# PiLoraGatewayV2_6.net
KiCad netlist of a schematic drawn in EAGLE
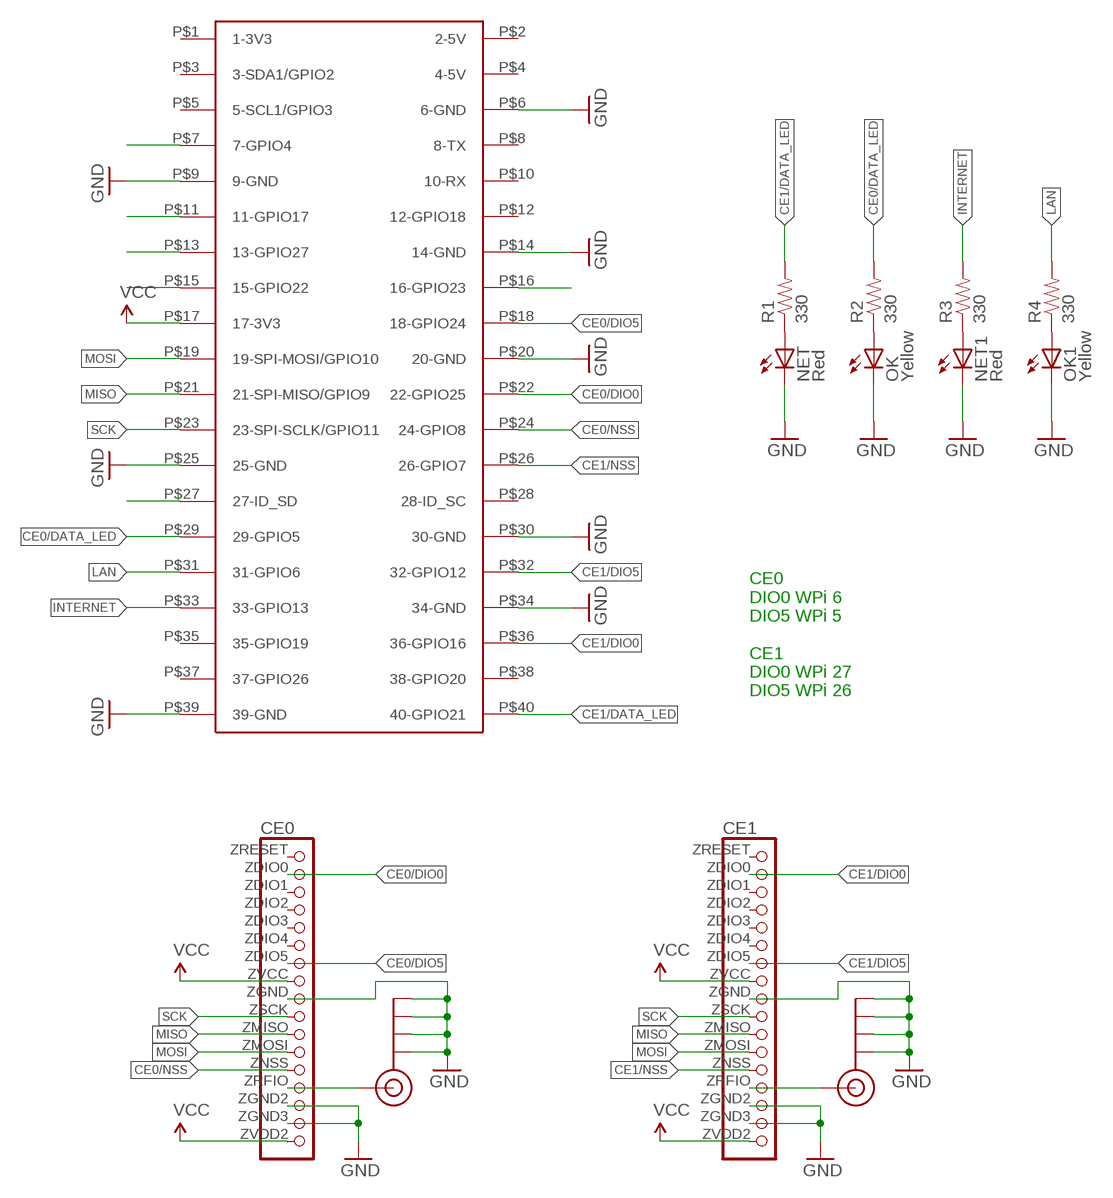
[diagram p0: schematic, sheet 1]

(export (version "E")
  (design (tool "Eeschema 10.0.6"))
  (components
    (comp (ref "CE0")
      (value "DRF1278F_BKOUTDP1276")
      (footprint "eagle-import:ANYLINK_DP1276")
      (libsource (lib "eagle-import") (part "DRF1278F_BKOUTDP1276"))
    )
    (comp (ref "CE1")
      (value "DRF1278F_BKOUTDP1276")
      (footprint "eagle-import:ANYLINK_DP1276")
      (libsource (lib "eagle-import") (part "DRF1278F_BKOUTDP1276"))
    )
    (comp (ref "J$1")
      (value "SMA_EDGE")
      (footprint "eagle-import:SMA-EDGE")
      (libsource (lib "eagle-import") (part "SMA_EDGE"))
    )
    (comp (ref "J$2")
      (value "SMA_EDGE")
      (footprint "eagle-import:SMA-EDGE")
      (libsource (lib "eagle-import") (part "SMA_EDGE"))
    )
    (comp (ref "NET")
      (value "Red")
      (footprint "eagle-import:LED-0603")
      (libsource (lib "eagle-import") (part "LED0603"))
    )
    (comp (ref "NET1")
      (value "Red")
      (footprint "eagle-import:LED-0603")
      (libsource (lib "eagle-import") (part "LED0603"))
    )
    (comp (ref "OK")
      (value "Yellow")
      (footprint "eagle-import:LED-0603")
      (libsource (lib "eagle-import") (part "LED0603"))
    )
    (comp (ref "OK1")
      (value "Yellow")
      (footprint "eagle-import:LED-0603")
      (libsource (lib "eagle-import") (part "LED0603"))
    )
    (comp (ref "R1")
      (value "330")
      (footprint "eagle-import:0603-RES")
      (libsource (lib "eagle-import") (part "RESISTOR0603-RES"))
    )
    (comp (ref "R2")
      (value "330")
      (footprint "eagle-import:0603-RES")
      (libsource (lib "eagle-import") (part "RESISTOR0603-RES"))
    )
    (comp (ref "R3")
      (value "330")
      (footprint "eagle-import:0603-RES")
      (libsource (lib "eagle-import") (part "RESISTOR0603-RES"))
    )
    (comp (ref "R4")
      (value "330")
      (footprint "eagle-import:0603-RES")
      (libsource (lib "eagle-import") (part "RESISTOR0603-RES"))
    )
    (comp (ref "U$1")
      (value "RASPBERRY-PI+")
      (footprint "eagle-import:RASPBERRY-PI-PLUS-CAM_NOTCH")
      (libsource (lib "eagle-import") (part "RASPBERRY-PI+"))
    )
  )
  (nets
    (net (code "1") (name "CE0{slash}DATA_LED") (class "Default")
      (node (ref "R2") (pin "2") (pinfunction "2_2") (pintype "passive"))
      (node (ref "U$1") (pin "P$29") (pinfunction "29-GPIO5_P$29") (pintype "bidirectional"))
    )
    (net (code "2") (name "CE0{slash}DIO0") (class "Default")
      (node (ref "CE0") (pin "ZDIO0") (pinfunction "DIO0_ZDIO0") (pintype "passive"))
      (node (ref "U$1") (pin "P$22") (pinfunction "22-GPIO25_P$22") (pintype "bidirectional"))
    )
    (net (code "3") (name "CE0{slash}DIO5") (class "Default")
      (node (ref "CE0") (pin "ZDIO5") (pinfunction "DIO5_ZDIO5") (pintype "passive"))
      (node (ref "U$1") (pin "P$18") (pinfunction "18-GPIO24_P$18") (pintype "bidirectional"))
    )
    (net (code "4") (name "CE0{slash}NSS") (class "Default")
      (node (ref "CE0") (pin "ZNSS") (pinfunction "NSS_ZNSS") (pintype "passive"))
      (node (ref "U$1") (pin "P$24") (pinfunction "24-GPIO8_P$24") (pintype "bidirectional"))
    )
    (net (code "5") (name "CE1{slash}DATA_LED") (class "Default")
      (node (ref "R1") (pin "2") (pinfunction "2_2") (pintype "passive"))
      (node (ref "U$1") (pin "P$40") (pinfunction "40-GPIO21_P$40") (pintype "bidirectional"))
    )
    (net (code "6") (name "CE1{slash}DIO0") (class "Default")
      (node (ref "CE1") (pin "ZDIO0") (pinfunction "DIO0_ZDIO0") (pintype "passive"))
      (node (ref "U$1") (pin "P$36") (pinfunction "36-GPIO16_P$36") (pintype "bidirectional"))
    )
    (net (code "7") (name "CE1{slash}DIO5") (class "Default")
      (node (ref "CE1") (pin "ZDIO5") (pinfunction "DIO5_ZDIO5") (pintype "passive"))
      (node (ref "U$1") (pin "P$32") (pinfunction "32-GPIO12_P$32") (pintype "bidirectional"))
    )
    (net (code "8") (name "CE1{slash}NSS") (class "Default")
      (node (ref "CE1") (pin "ZNSS") (pinfunction "NSS_ZNSS") (pintype "passive"))
      (node (ref "U$1") (pin "P$26") (pinfunction "26-GPIO7_P$26") (pintype "bidirectional"))
    )
    (net (code "9") (name "GND") (class "Default")
      (node (ref "CE0") (pin "ZGND") (pinfunction "GND_ZGND") (pintype "passive"))
      (node (ref "CE0") (pin "ZGND2") (pinfunction "RGND1_ZGND2") (pintype "passive"))
      (node (ref "CE0") (pin "ZGND3") (pinfunction "RGND2_ZGND3") (pintype "passive"))
      (node (ref "CE1") (pin "ZGND") (pinfunction "GND_ZGND") (pintype "passive"))
      (node (ref "CE1") (pin "ZGND2") (pinfunction "RGND1_ZGND2") (pintype "passive"))
      (node (ref "CE1") (pin "ZGND3") (pinfunction "RGND2_ZGND3") (pintype "passive"))
      (node (ref "J$1") (pin "GND@0") (pinfunction "GND_GND@0") (pintype "bidirectional"))
      (node (ref "J$1") (pin "GND@1") (pinfunction "GND_GND@1") (pintype "bidirectional"))
      (node (ref "J$1") (pin "GND@2") (pinfunction "GND_GND@2") (pintype "bidirectional"))
      (node (ref "J$1") (pin "GND@3") (pinfunction "GND_GND@3") (pintype "bidirectional"))
      (node (ref "J$2") (pin "GND@0") (pinfunction "GND_GND@0") (pintype "bidirectional"))
      (node (ref "J$2") (pin "GND@1") (pinfunction "GND_GND@1") (pintype "bidirectional"))
      (node (ref "J$2") (pin "GND@2") (pinfunction "GND_GND@2") (pintype "bidirectional"))
      (node (ref "J$2") (pin "GND@3") (pinfunction "GND_GND@3") (pintype "bidirectional"))
      (node (ref "NET") (pin "C") (pinfunction "C_C") (pintype "passive"))
      (node (ref "NET1") (pin "C") (pinfunction "C_C") (pintype "passive"))
      (node (ref "OK") (pin "C") (pinfunction "C_C") (pintype "passive"))
      (node (ref "OK1") (pin "C") (pinfunction "C_C") (pintype "passive"))
      (node (ref "U$1") (pin "P$14") (pinfunction "14-GND_P$14") (pintype "bidirectional"))
      (node (ref "U$1") (pin "P$20") (pinfunction "20-GND_P$20") (pintype "bidirectional"))
      (node (ref "U$1") (pin "P$25") (pinfunction "25-GND_P$25") (pintype "bidirectional"))
      (node (ref "U$1") (pin "P$30") (pinfunction "30-GND_P$30") (pintype "bidirectional"))
      (node (ref "U$1") (pin "P$34") (pinfunction "34-GND_P$34") (pintype "bidirectional"))
      (node (ref "U$1") (pin "P$39") (pinfunction "39-GND_P$39") (pintype "bidirectional"))
      (node (ref "U$1") (pin "P$6") (pinfunction "6-GND_P$6") (pintype "bidirectional"))
      (node (ref "U$1") (pin "P$9") (pinfunction "9-GND_P$9") (pintype "bidirectional"))
    )
    (net (code "10") (name "INTERNET") (class "Default")
      (node (ref "R3") (pin "2") (pinfunction "2_2") (pintype "passive"))
      (node (ref "U$1") (pin "P$33") (pinfunction "33-GPIO13_P$33") (pintype "bidirectional"))
    )
    (net (code "11") (name "LAN") (class "Default")
      (node (ref "R4") (pin "2") (pinfunction "2_2") (pintype "passive"))
      (node (ref "U$1") (pin "P$31") (pinfunction "31-GPIO6_P$31") (pintype "bidirectional"))
    )
    (net (code "12") (name "MISO") (class "Default")
      (node (ref "CE0") (pin "ZMISO") (pinfunction "MISO_ZMISO") (pintype "passive"))
      (node (ref "CE1") (pin "ZMISO") (pinfunction "MISO_ZMISO") (pintype "passive"))
      (node (ref "U$1") (pin "P$21") (pinfunction "21-SPI-MISO/GPIO9_P$21") (pintype "bidirectional"))
    )
    (net (code "13") (name "MOSI") (class "Default")
      (node (ref "CE0") (pin "ZMOSI") (pinfunction "MOSI_ZMOSI") (pintype "passive"))
      (node (ref "CE1") (pin "ZMOSI") (pinfunction "MOSI_ZMOSI") (pintype "passive"))
      (node (ref "U$1") (pin "P$19") (pinfunction "19-SPI-MOSI/GPIO10_P$19") (pintype "bidirectional"))
    )
    (net (code "14") (name "Net-(CE0-RFIO)") (class "Default")
      (node (ref "CE0") (pin "ZRFIO") (pinfunction "RFIO_ZRFIO") (pintype "passive"))
      (node (ref "J$1") (pin "SIG") (pinfunction "SIGNAL_SIG") (pintype "bidirectional"))
    )
    (net (code "15") (name "Net-(CE1-RFIO)") (class "Default")
      (node (ref "CE1") (pin "ZRFIO") (pinfunction "RFIO_ZRFIO") (pintype "passive"))
      (node (ref "J$2") (pin "SIG") (pinfunction "SIGNAL_SIG") (pintype "bidirectional"))
    )
    (net (code "16") (name "Net-(NET-PadA)") (class "Default")
      (node (ref "NET") (pin "A") (pinfunction "A_A") (pintype "passive"))
      (node (ref "R1") (pin "1") (pinfunction "1_1") (pintype "passive"))
    )
    (net (code "17") (name "Net-(NET1-PadA)") (class "Default")
      (node (ref "NET1") (pin "A") (pinfunction "A_A") (pintype "passive"))
      (node (ref "R3") (pin "1") (pinfunction "1_1") (pintype "passive"))
    )
    (net (code "18") (name "Net-(OK-PadA)") (class "Default")
      (node (ref "OK") (pin "A") (pinfunction "A_A") (pintype "passive"))
      (node (ref "R2") (pin "1") (pinfunction "1_1") (pintype "passive"))
    )
    (net (code "19") (name "Net-(OK1-PadA)") (class "Default")
      (node (ref "OK1") (pin "A") (pinfunction "A_A") (pintype "passive"))
      (node (ref "R4") (pin "1") (pinfunction "1_1") (pintype "passive"))
    )
    (net (code "20") (name "SCK") (class "Default")
      (node (ref "CE0") (pin "ZSCK") (pinfunction "SCK_ZSCK") (pintype "passive"))
      (node (ref "CE1") (pin "ZSCK") (pinfunction "SCK_ZSCK") (pintype "passive"))
      (node (ref "U$1") (pin "P$23") (pinfunction "23-SPI-SCLK/GPIO11_P$23") (pintype "bidirectional"))
    )
    (net (code "21") (name "VCC") (class "Default")
      (node (ref "CE0") (pin "ZVCC") (pinfunction "VCC_ZVCC") (pintype "passive"))
      (node (ref "CE0") (pin "ZVDD2") (pinfunction "VCC2_ZVDD2") (pintype "passive"))
      (node (ref "CE1") (pin "ZVCC") (pinfunction "VCC_ZVCC") (pintype "passive"))
      (node (ref "CE1") (pin "ZVDD2") (pinfunction "VCC2_ZVDD2") (pintype "passive"))
      (node (ref "U$1") (pin "P$17") (pinfunction "17-3V3_P$17") (pintype "bidirectional"))
    )
    (net (code "22") (name "unconnected-(CE0-DIO1-PadZDIO1)") (class "Default")
      (node (ref "CE0") (pin "ZDIO1") (pinfunction "DIO1_ZDIO1") (pintype "passive"))
    )
    (net (code "23") (name "unconnected-(CE0-DIO2-PadZDIO2)") (class "Default")
      (node (ref "CE0") (pin "ZDIO2") (pinfunction "DIO2_ZDIO2") (pintype "passive"))
    )
    (net (code "24") (name "unconnected-(CE0-DIO3-PadZDIO3)") (class "Default")
      (node (ref "CE0") (pin "ZDIO3") (pinfunction "DIO3_ZDIO3") (pintype "passive"))
    )
    (net (code "25") (name "unconnected-(CE0-DIO4-PadZDIO4)") (class "Default")
      (node (ref "CE0") (pin "ZDIO4") (pinfunction "DIO4_ZDIO4") (pintype "passive"))
    )
    (net (code "26") (name "unconnected-(CE0-RESET-PadZRESET)") (class "Default")
      (node (ref "CE0") (pin "ZRESET") (pinfunction "RESET_ZRESET") (pintype "passive"))
    )
    (net (code "27") (name "unconnected-(CE1-DIO1-PadZDIO1)") (class "Default")
      (node (ref "CE1") (pin "ZDIO1") (pinfunction "DIO1_ZDIO1") (pintype "passive"))
    )
    (net (code "28") (name "unconnected-(CE1-DIO2-PadZDIO2)") (class "Default")
      (node (ref "CE1") (pin "ZDIO2") (pinfunction "DIO2_ZDIO2") (pintype "passive"))
    )
    (net (code "29") (name "unconnected-(CE1-DIO3-PadZDIO3)") (class "Default")
      (node (ref "CE1") (pin "ZDIO3") (pinfunction "DIO3_ZDIO3") (pintype "passive"))
    )
    (net (code "30") (name "unconnected-(CE1-DIO4-PadZDIO4)") (class "Default")
      (node (ref "CE1") (pin "ZDIO4") (pinfunction "DIO4_ZDIO4") (pintype "passive"))
    )
    (net (code "31") (name "unconnected-(CE1-RESET-PadZRESET)") (class "Default")
      (node (ref "CE1") (pin "ZRESET") (pinfunction "RESET_ZRESET") (pintype "passive"))
    )
    (net (code "32") (name "unconnected-(U$1-1-3V3-PadP$1)") (class "Default")
      (node (ref "U$1") (pin "P$1") (pinfunction "1-3V3_P$1") (pintype "bidirectional"))
    )
    (net (code "33") (name "unconnected-(U$1-2-5V-PadP$2)") (class "Default")
      (node (ref "U$1") (pin "P$2") (pinfunction "2-5V_P$2") (pintype "bidirectional"))
    )
    (net (code "34") (name "unconnected-(U$1-3-SDA1{slash}GPIO2-PadP$3)") (class "Default")
      (node (ref "U$1") (pin "P$3") (pinfunction "3-SDA1/GPIO2_P$3") (pintype "bidirectional"))
    )
    (net (code "35") (name "unconnected-(U$1-4-5V-PadP$4)") (class "Default")
      (node (ref "U$1") (pin "P$4") (pinfunction "4-5V_P$4") (pintype "bidirectional"))
    )
    (net (code "36") (name "unconnected-(U$1-5-SCL1{slash}GPIO3-PadP$5)") (class "Default")
      (node (ref "U$1") (pin "P$5") (pinfunction "5-SCL1/GPIO3_P$5") (pintype "bidirectional"))
    )
    (net (code "37") (name "unconnected-(U$1-7-GPIO4-PadP$7)") (class "Default")
      (node (ref "U$1") (pin "P$7") (pinfunction "7-GPIO4_P$7") (pintype "bidirectional"))
    )
    (net (code "38") (name "unconnected-(U$1-8-TX-PadP$8)") (class "Default")
      (node (ref "U$1") (pin "P$8") (pinfunction "8-TX_P$8") (pintype "bidirectional"))
    )
    (net (code "39") (name "unconnected-(U$1-10-RX-PadP$10)") (class "Default")
      (node (ref "U$1") (pin "P$10") (pinfunction "10-RX_P$10") (pintype "bidirectional"))
    )
    (net (code "40") (name "unconnected-(U$1-11-GPIO17-PadP$11)") (class "Default")
      (node (ref "U$1") (pin "P$11") (pinfunction "11-GPIO17_P$11") (pintype "bidirectional"))
    )
    (net (code "41") (name "unconnected-(U$1-12-GPIO18-PadP$12)") (class "Default")
      (node (ref "U$1") (pin "P$12") (pinfunction "12-GPIO18_P$12") (pintype "bidirectional"))
    )
    (net (code "42") (name "unconnected-(U$1-13-GPIO27-PadP$13)") (class "Default")
      (node (ref "U$1") (pin "P$13") (pinfunction "13-GPIO27_P$13") (pintype "bidirectional"))
    )
    (net (code "43") (name "unconnected-(U$1-15-GPIO22-PadP$15)") (class "Default")
      (node (ref "U$1") (pin "P$15") (pinfunction "15-GPIO22_P$15") (pintype "bidirectional"))
    )
    (net (code "44") (name "unconnected-(U$1-16-GPIO23-PadP$16)") (class "Default")
      (node (ref "U$1") (pin "P$16") (pinfunction "16-GPIO23_P$16") (pintype "bidirectional"))
    )
    (net (code "45") (name "unconnected-(U$1-27-ID_SD-PadP$27)") (class "Default")
      (node (ref "U$1") (pin "P$27") (pinfunction "27-ID_SD_P$27") (pintype "bidirectional"))
    )
    (net (code "46") (name "unconnected-(U$1-28-ID_SC-PadP$28)") (class "Default")
      (node (ref "U$1") (pin "P$28") (pinfunction "28-ID_SC_P$28") (pintype "bidirectional"))
    )
    (net (code "47") (name "unconnected-(U$1-35-GPIO19-PadP$35)") (class "Default")
      (node (ref "U$1") (pin "P$35") (pinfunction "35-GPIO19_P$35") (pintype "bidirectional"))
    )
    (net (code "48") (name "unconnected-(U$1-37-GPIO26-PadP$37)") (class "Default")
      (node (ref "U$1") (pin "P$37") (pinfunction "37-GPIO26_P$37") (pintype "bidirectional"))
    )
    (net (code "49") (name "unconnected-(U$1-38-GPIO20-PadP$38)") (class "Default")
      (node (ref "U$1") (pin "P$38") (pinfunction "38-GPIO20_P$38") (pintype "bidirectional"))
    )
  )
)
